# virtual_wall_lp.net
KiCad netlist of a schematic drawn in EAGLE
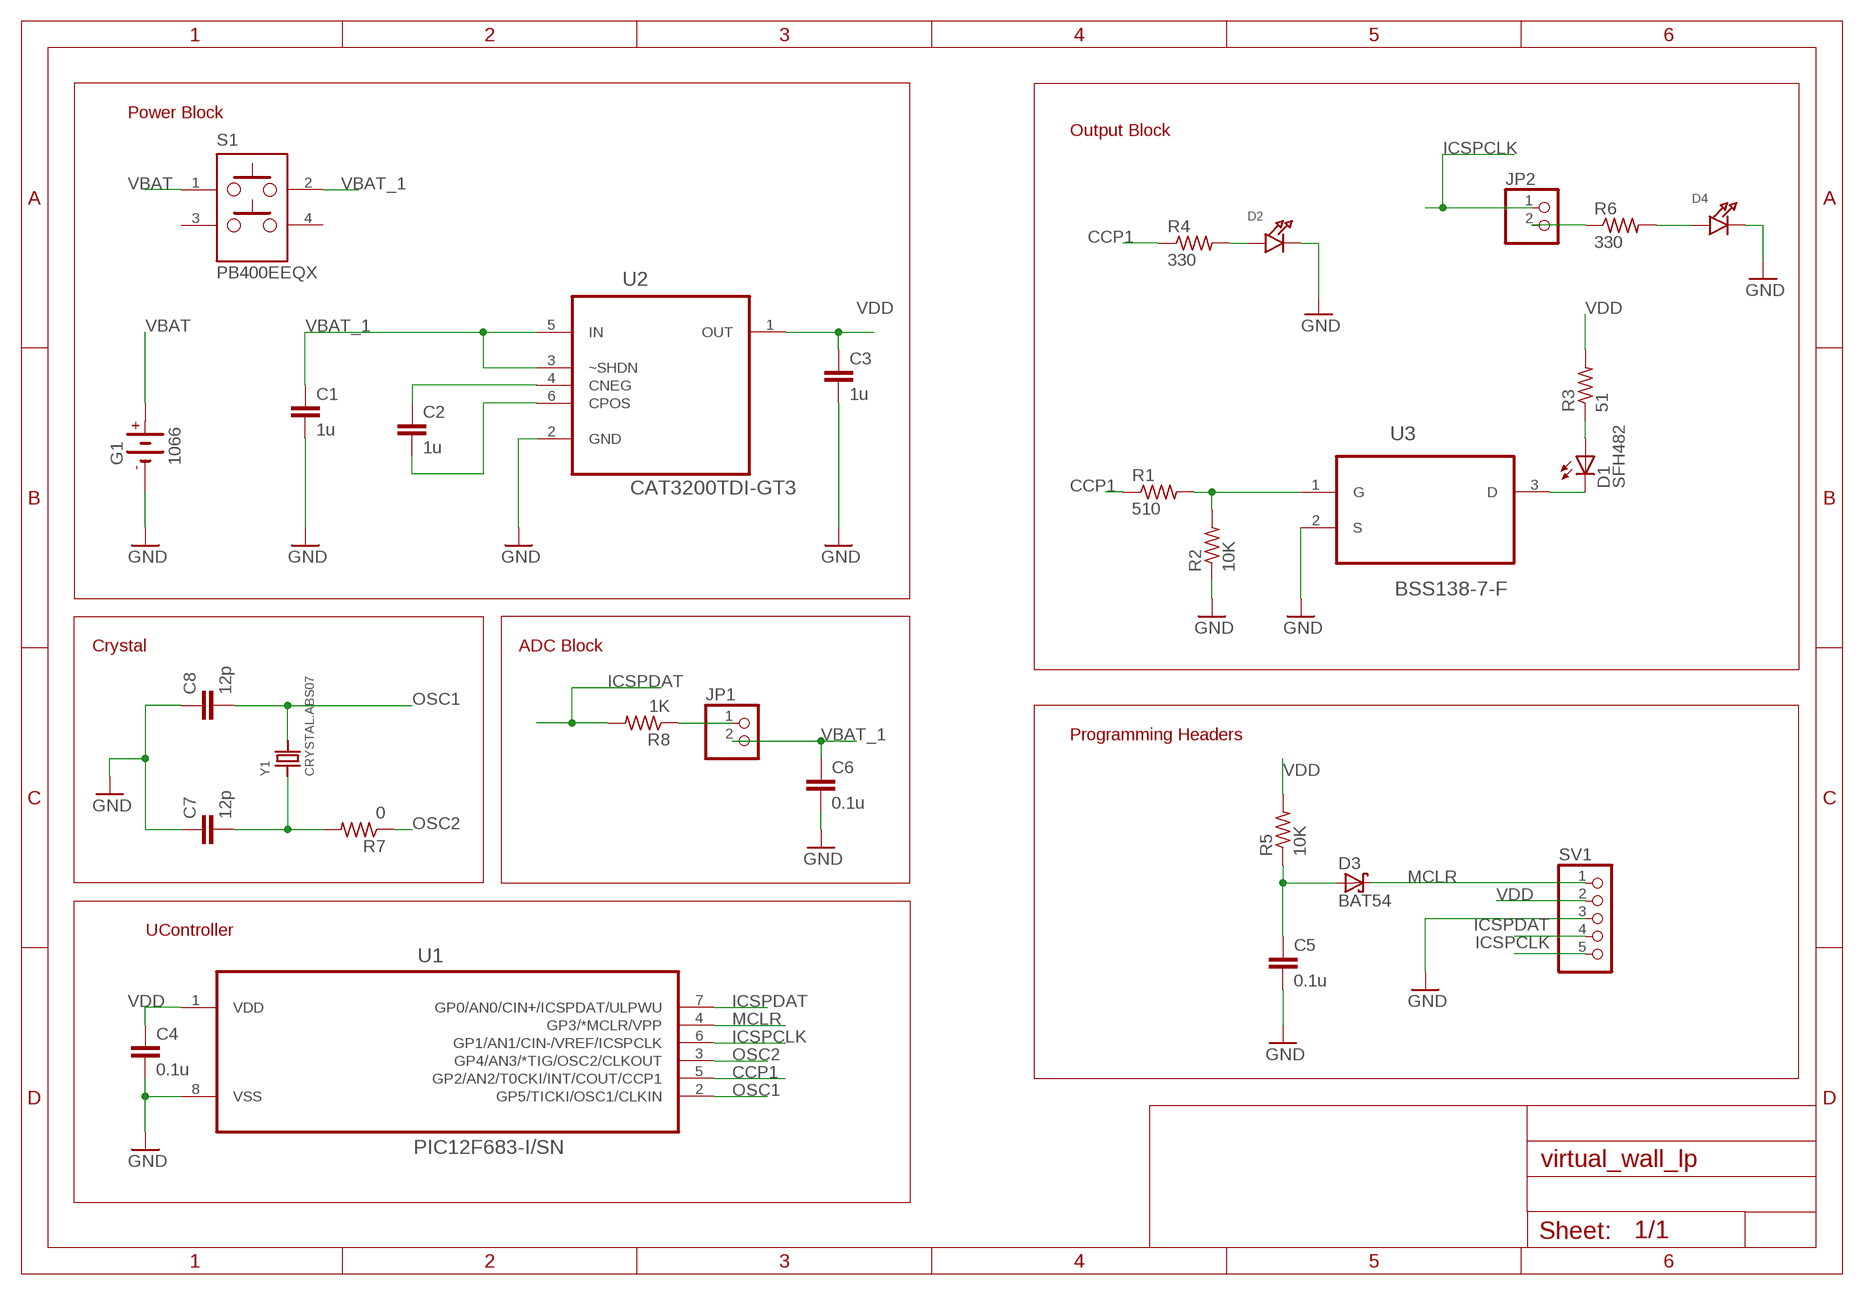
[diagram p0: schematic, sheet 1]

(export (version "E")
  (design (tool "Eeschema 10.0.6"))
  (components
    (comp (ref "C1")
      (value "1u")
      (footprint "eagle-import:C0603")
      (libsource (lib "eagle-import") (part "C-EUC0603"))
    )
    (comp (ref "C2")
      (value "1u")
      (footprint "eagle-import:C0603")
      (libsource (lib "eagle-import") (part "C-EUC0603"))
    )
    (comp (ref "C3")
      (value "1u")
      (footprint "eagle-import:C0603")
      (libsource (lib "eagle-import") (part "C-EUC0603"))
    )
    (comp (ref "C4")
      (value "0.1u")
      (footprint "eagle-import:C0603")
      (libsource (lib "eagle-import") (part "C-EUC0603"))
    )
    (comp (ref "C5")
      (value "0.1u")
      (footprint "eagle-import:C0603")
      (libsource (lib "eagle-import") (part "C-EUC0603"))
    )
    (comp (ref "C6")
      (value "0.1u")
      (footprint "eagle-import:C0603")
      (libsource (lib "eagle-import") (part "C-EUC0603"))
    )
    (comp (ref "C7")
      (value "12p")
      (footprint "eagle-import:C0603")
      (libsource (lib "eagle-import") (part "C-EUC0603"))
    )
    (comp (ref "C8")
      (value "12p")
      (footprint "eagle-import:C0603")
      (libsource (lib "eagle-import") (part "C-EUC0603"))
    )
    (comp (ref "D1")
      (value "SFH482")
      (footprint "eagle-import:SFH482")
      (libsource (lib "eagle-import") (part "SFH482"))
    )
    (comp (ref "D2")
      (value "LED1206")
      (footprint "eagle-import:CHIPLED_1206")
      (libsource (lib "eagle-import") (part "LED1206"))
    )
    (comp (ref "D3")
      (value "BAT54")
      (footprint "eagle-import:SOT23")
      (libsource (lib "eagle-import") (part "BAT54"))
    )
    (comp (ref "D4")
      (value "LED1206")
      (footprint "eagle-import:CHIPLED_1206")
      (libsource (lib "eagle-import") (part "LED1206"))
    )
    (comp (ref "G1")
      (value "1066")
      (footprint "eagle-import:1066")
      (fields (field (name "MF") "Greenlee Communications"))
      (libsource (lib "eagle-import") (part "1066"))
    )
    (comp (ref "JP1")
      (value "PINHD-1X2")
      (footprint "eagle-import:1X02")
      (libsource (lib "eagle-import") (part "PINHD-1X2"))
    )
    (comp (ref "JP2")
      (value "PINHD-1X2")
      (footprint "eagle-import:1X02")
      (libsource (lib "eagle-import") (part "PINHD-1X2"))
    )
    (comp (ref "R1")
      (value "510")
      (footprint "eagle-import:R0603")
      (libsource (lib "eagle-import") (part "R-US_R0603"))
    )
    (comp (ref "R2")
      (value "10K")
      (footprint "eagle-import:R0603")
      (libsource (lib "eagle-import") (part "R-US_R0603"))
    )
    (comp (ref "R3")
      (value "51")
      (footprint "eagle-import:R0603")
      (libsource (lib "eagle-import") (part "R-US_R0603"))
    )
    (comp (ref "R4")
      (value "330")
      (footprint "eagle-import:R0603")
      (libsource (lib "eagle-import") (part "R-US_R0603"))
    )
    (comp (ref "R5")
      (value "10K")
      (footprint "eagle-import:R0603")
      (libsource (lib "eagle-import") (part "R-US_R0603"))
    )
    (comp (ref "R6")
      (value "330")
      (footprint "eagle-import:R0603")
      (libsource (lib "eagle-import") (part "R-US_R0603"))
    )
    (comp (ref "R7")
      (value "0")
      (footprint "eagle-import:R0603")
      (libsource (lib "eagle-import") (part "R-US_R0603"))
    )
    (comp (ref "R8")
      (value "1K")
      (footprint "eagle-import:R0603")
      (libsource (lib "eagle-import") (part "R-US_R0603"))
    )
    (comp (ref "S1")
      (value "PB400EEQX")
      (footprint "eagle-import:SW_PB400EEQX")
      (fields (field (name "MF") "E-Switch"))
      (libsource (lib "eagle-import") (part "PB400EEQX"))
    )
    (comp (ref "SV1")
      (value "PINHD-1X5")
      (footprint "eagle-import:1X05")
      (libsource (lib "eagle-import") (part "PINHD-1X5"))
    )
    (comp (ref "U1")
      (value "PIC12F683-I/SN")
      (footprint "eagle-import:SOIC127P600X175-8N")
      (libsource (lib "eagle-import") (part "PIC12F683-I/SN"))
    )
    (comp (ref "U2")
      (value "CAT3200TDI-GT3")
      (footprint "eagle-import:SOT95P280X100-6N")
      (fields (field (name "MF") "ON Semiconductor"))
      (libsource (lib "eagle-import") (part "CAT3200TDI-GT3"))
    )
    (comp (ref "U3")
      (value "BSS138-7-F")
      (footprint "eagle-import:SOT95P240X110-3N")
      (libsource (lib "eagle-import") (part "BSS138-7-F"))
    )
    (comp (ref "Y1")
      (value "CRYSTAL.ABS07")
      (footprint "eagle-import:ABS07")
      (libsource (lib "eagle-import") (part "CRYSTAL.ABS07"))
    )
  )
  (nets
    (net (code "1") (name "/CCP1") (class "Default")
      (node (ref "R1") (pin "1") (pinfunction "1_1") (pintype "passive"))
      (node (ref "R4") (pin "1") (pinfunction "1_1") (pintype "passive"))
      (node (ref "U1") (pin "5") (pinfunction "GP2/AN2/T0CKI/INT/COUT/CCP1_5") (pintype "bidirectional"))
    )
    (net (code "2") (name "/ICSPCLK") (class "Default")
      (node (ref "JP2") (pin "1") (pinfunction "1_1") (pintype "passive"))
      (node (ref "SV1") (pin "5") (pinfunction "5_5") (pintype "passive"))
      (node (ref "U1") (pin "6") (pinfunction "GP1/AN1/CIN-/VREF/ICSPCLK_6") (pintype "bidirectional"))
    )
    (net (code "3") (name "/ICSPDAT") (class "Default")
      (node (ref "R8") (pin "2") (pinfunction "2_2") (pintype "passive"))
      (node (ref "SV1") (pin "4") (pinfunction "4_4") (pintype "passive"))
      (node (ref "U1") (pin "7") (pinfunction "GP0/AN0/CIN+/ICSPDAT/ULPWU_7") (pintype "bidirectional"))
    )
    (net (code "4") (name "/MCLR") (class "Default")
      (node (ref "D3") (pin "3") (pinfunction "K_3") (pintype "passive"))
      (node (ref "SV1") (pin "1") (pinfunction "1_1") (pintype "passive"))
      (node (ref "U1") (pin "4") (pinfunction "GP3/*MCLR/VPP_4") (pintype "bidirectional"))
    )
    (net (code "5") (name "/OSC1") (class "Default")
      (node (ref "C8") (pin "2") (pinfunction "2_2") (pintype "passive"))
      (node (ref "U1") (pin "2") (pinfunction "GP5/TICKI/OSC1/CLKIN_2") (pintype "bidirectional"))
      (node (ref "Y1") (pin "2") (pinfunction "2_2") (pintype "passive"))
    )
    (net (code "6") (name "/OSC2") (class "Default")
      (node (ref "R7") (pin "1") (pinfunction "1_1") (pintype "passive"))
      (node (ref "U1") (pin "3") (pinfunction "GP4/AN3/*TIG/OSC2/CLKOUT_3") (pintype "bidirectional"))
    )
    (net (code "7") (name "/VBAT") (class "Default")
      (node (ref "G1") (pin "+") (pinfunction "+_+") (pintype "passive"))
      (node (ref "S1") (pin "1") (pinfunction "1_1") (pintype "passive"))
    )
    (net (code "8") (name "/VBAT_1") (class "Default")
      (node (ref "C1") (pin "1") (pinfunction "1_1") (pintype "passive"))
      (node (ref "C6") (pin "1") (pinfunction "1_1") (pintype "passive"))
      (node (ref "JP1") (pin "2") (pinfunction "2_2") (pintype "passive"))
      (node (ref "S1") (pin "2") (pinfunction "2_2") (pintype "passive"))
      (node (ref "U2") (pin "3") (pinfunction "~{SHDN}_3") (pintype "input"))
      (node (ref "U2") (pin "5") (pinfunction "IN_5") (pintype "input"))
    )
    (net (code "9") (name "/VDD") (class "Default")
      (node (ref "C3") (pin "1") (pinfunction "1_1") (pintype "passive"))
      (node (ref "C4") (pin "1") (pinfunction "1_1") (pintype "passive"))
      (node (ref "R3") (pin "2") (pinfunction "2_2") (pintype "passive"))
      (node (ref "R5") (pin "2") (pinfunction "2_2") (pintype "passive"))
      (node (ref "SV1") (pin "2") (pinfunction "2_2") (pintype "passive"))
      (node (ref "U1") (pin "1") (pinfunction "VDD_1") (pintype "power_in"))
      (node (ref "U2") (pin "1") (pinfunction "OUT_1") (pintype "output"))
    )
    (net (code "10") (name "GND") (class "Default")
      (node (ref "C1") (pin "2") (pinfunction "2_2") (pintype "passive"))
      (node (ref "C3") (pin "2") (pinfunction "2_2") (pintype "passive"))
      (node (ref "C4") (pin "2") (pinfunction "2_2") (pintype "passive"))
      (node (ref "C5") (pin "2") (pinfunction "2_2") (pintype "passive"))
      (node (ref "C6") (pin "2") (pinfunction "2_2") (pintype "passive"))
      (node (ref "C7") (pin "1") (pinfunction "1_1") (pintype "passive"))
      (node (ref "C8") (pin "1") (pinfunction "1_1") (pintype "passive"))
      (node (ref "D2") (pin "C") (pinfunction "C_C") (pintype "passive"))
      (node (ref "D4") (pin "C") (pinfunction "C_C") (pintype "passive"))
      (node (ref "G1") (pin "-") (pinfunction "-_-") (pintype "passive"))
      (node (ref "R2") (pin "1") (pinfunction "1_1") (pintype "passive"))
      (node (ref "SV1") (pin "3") (pinfunction "3_3") (pintype "passive"))
      (node (ref "U1") (pin "8") (pinfunction "VSS_8") (pintype "passive"))
      (node (ref "U2") (pin "2") (pinfunction "GND_2") (pintype "passive"))
      (node (ref "U3") (pin "2") (pinfunction "S_2") (pintype "passive"))
    )
    (net (code "11") (name "Net-(C7-Pad2)") (class "Default")
      (node (ref "C7") (pin "2") (pinfunction "2_2") (pintype "passive"))
      (node (ref "R7") (pin "2") (pinfunction "2_2") (pintype "passive"))
      (node (ref "Y1") (pin "1") (pinfunction "1_1") (pintype "passive"))
    )
    (net (code "12") (name "Net-(D1-C)") (class "Default")
      (node (ref "D1") (pin "K") (pinfunction "C_K") (pintype "passive"))
      (node (ref "U3") (pin "3") (pinfunction "D_3") (pintype "passive"))
    )
    (net (code "13") (name "Net-(D1-PadA)") (class "Default")
      (node (ref "D1") (pin "A") (pinfunction "A_A") (pintype "passive"))
      (node (ref "R3") (pin "1") (pinfunction "1_1") (pintype "passive"))
    )
    (net (code "14") (name "Net-(D2-PadA)") (class "Default")
      (node (ref "D2") (pin "A") (pinfunction "A_A") (pintype "passive"))
      (node (ref "R4") (pin "2") (pinfunction "2_2") (pintype "passive"))
    )
    (net (code "15") (name "Net-(D3-A)") (class "Default")
      (node (ref "C5") (pin "1") (pinfunction "1_1") (pintype "passive"))
      (node (ref "D3") (pin "1") (pinfunction "A_1") (pintype "passive"))
      (node (ref "R5") (pin "1") (pinfunction "1_1") (pintype "passive"))
    )
    (net (code "16") (name "Net-(D4-PadA)") (class "Default")
      (node (ref "D4") (pin "A") (pinfunction "A_A") (pintype "passive"))
      (node (ref "R6") (pin "2") (pinfunction "2_2") (pintype "passive"))
    )
    (net (code "17") (name "Net-(JP1-Pad1)") (class "Default")
      (node (ref "JP1") (pin "1") (pinfunction "1_1") (pintype "passive"))
      (node (ref "R8") (pin "1") (pinfunction "1_1") (pintype "passive"))
    )
    (net (code "18") (name "Net-(JP2-Pad2)") (class "Default")
      (node (ref "JP2") (pin "2") (pinfunction "2_2") (pintype "passive"))
      (node (ref "R6") (pin "1") (pinfunction "1_1") (pintype "passive"))
    )
    (net (code "19") (name "Net-(U2-CNEG)") (class "Default")
      (node (ref "C2") (pin "1") (pinfunction "1_1") (pintype "passive"))
      (node (ref "U2") (pin "4") (pinfunction "CNEG_4") (pintype "input"))
    )
    (net (code "20") (name "Net-(U2-CPOS)") (class "Default")
      (node (ref "C2") (pin "2") (pinfunction "2_2") (pintype "passive"))
      (node (ref "U2") (pin "6") (pinfunction "CPOS_6") (pintype "input"))
    )
    (net (code "21") (name "Net-(U3-G)") (class "Default")
      (node (ref "R1") (pin "2") (pinfunction "2_2") (pintype "passive"))
      (node (ref "R2") (pin "2") (pinfunction "2_2") (pintype "passive"))
      (node (ref "U3") (pin "1") (pinfunction "G_1") (pintype "passive"))
    )
    (net (code "22") (name "unconnected-(S1-Pad3)") (class "Default")
      (node (ref "S1") (pin "3") (pinfunction "3_3") (pintype "passive"))
    )
    (net (code "23") (name "unconnected-(S1-Pad4)") (class "Default")
      (node (ref "S1") (pin "4") (pinfunction "4_4") (pintype "passive"))
    )
  )
)
